# BigClown_Sensor_adapter_v0_2.net
KiCad netlist of a schematic drawn in EAGLE
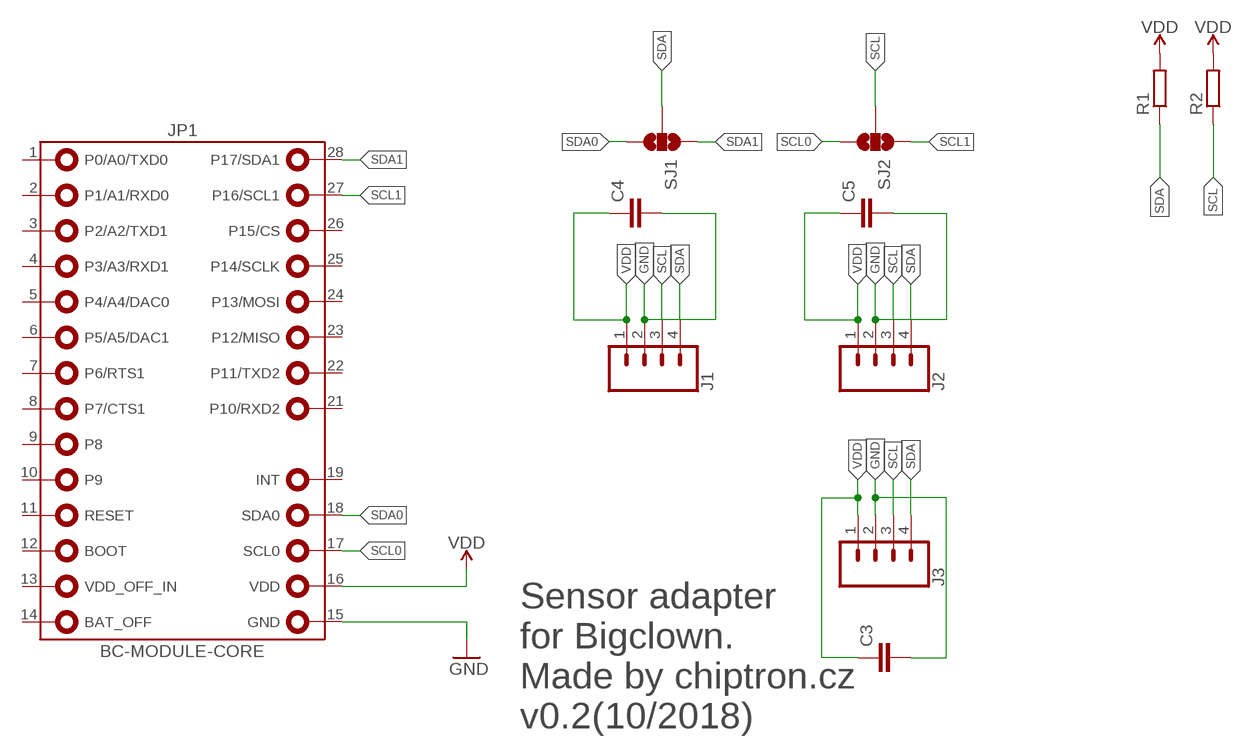
[diagram p0: schematic, sheet 1]

(export (version "E")
  (design (tool "Eeschema 10.0.6"))
  (components
    (comp (ref "C3")
      (value "C-EUC0805")
      (footprint "eagle-import:C0805")
      (libsource (lib "eagle-import") (part "C-EUC0805"))
    )
    (comp (ref "C4")
      (value "C-EUC0805")
      (footprint "eagle-import:C0805")
      (libsource (lib "eagle-import") (part "C-EUC0805"))
    )
    (comp (ref "C5")
      (value "C-EUC0805")
      (footprint "eagle-import:C0805")
      (libsource (lib "eagle-import") (part "C-EUC0805"))
    )
    (comp (ref "J1")
      (value "CONN_04LONGPADS")
      (footprint "eagle-import:1X04_LONGPADS")
      (libsource (lib "eagle-import") (part "CONN_04LONGPADS"))
    )
    (comp (ref "J2")
      (value "CONN_04LONGPADS")
      (footprint "eagle-import:1X04_LONGPADS")
      (libsource (lib "eagle-import") (part "CONN_04LONGPADS"))
    )
    (comp (ref "J3")
      (value "CONN_04LONGPADS")
      (footprint "eagle-import:1X04_LONGPADS")
      (libsource (lib "eagle-import") (part "CONN_04LONGPADS"))
    )
    (comp (ref "JP1")
      (value "BC-MODULE-CORE")
      (footprint "eagle-import:BC-MODULE-CORE")
      (libsource (lib "eagle-import") (part "BC-MODULE-CORE"))
    )
    (comp (ref "R1")
      (value "R-EU_M0805")
      (footprint "eagle-import:M0805")
      (libsource (lib "eagle-import") (part "R-EU_M0805"))
    )
    (comp (ref "R2")
      (value "R-EU_M0805")
      (footprint "eagle-import:M0805")
      (libsource (lib "eagle-import") (part "R-EU_M0805"))
    )
    (comp (ref "SJ1")
      (value "SOLDERJUMPER_2WAYS")
      (footprint "eagle-import:SJ_3")
      (libsource (lib "eagle-import") (part "SOLDERJUMPER_2WAYS"))
    )
    (comp (ref "SJ2")
      (value "SOLDERJUMPER_2WAYS")
      (footprint "eagle-import:SJ_3")
      (libsource (lib "eagle-import") (part "SOLDERJUMPER_2WAYS"))
    )
  )
  (nets
    (net (code "1") (name "GND") (class "Default")
      (node (ref "C3") (pin "2") (pinfunction "2_2") (pintype "passive"))
      (node (ref "C4") (pin "2") (pinfunction "2_2") (pintype "passive"))
      (node (ref "C5") (pin "2") (pinfunction "2_2") (pintype "passive"))
      (node (ref "J1") (pin "2") (pinfunction "2_2") (pintype "passive"))
      (node (ref "J2") (pin "2") (pinfunction "2_2") (pintype "passive"))
      (node (ref "J3") (pin "2") (pinfunction "2_2") (pintype "passive"))
      (node (ref "JP1") (pin "15") (pinfunction "GND_15") (pintype "passive"))
    )
    (net (code "2") (name "SCL") (class "Default")
      (node (ref "J1") (pin "3") (pinfunction "3_3") (pintype "passive"))
      (node (ref "J2") (pin "3") (pinfunction "3_3") (pintype "passive"))
      (node (ref "J3") (pin "3") (pinfunction "3_3") (pintype "passive"))
      (node (ref "R2") (pin "1") (pinfunction "1_1") (pintype "passive"))
      (node (ref "SJ2") (pin "2") (pinfunction "2_2") (pintype "passive"))
    )
    (net (code "3") (name "SCL0") (class "Default")
      (node (ref "JP1") (pin "17") (pinfunction "SCL0_17") (pintype "passive"))
      (node (ref "SJ2") (pin "3") (pinfunction "3_3") (pintype "passive"))
    )
    (net (code "4") (name "SCL1") (class "Default")
      (node (ref "JP1") (pin "27") (pinfunction "P16/SCL1_27") (pintype "passive"))
      (node (ref "SJ2") (pin "1") (pinfunction "1_1") (pintype "passive"))
    )
    (net (code "5") (name "SDA") (class "Default")
      (node (ref "J1") (pin "4") (pinfunction "4_4") (pintype "passive"))
      (node (ref "J2") (pin "4") (pinfunction "4_4") (pintype "passive"))
      (node (ref "J3") (pin "4") (pinfunction "4_4") (pintype "passive"))
      (node (ref "R1") (pin "1") (pinfunction "1_1") (pintype "passive"))
      (node (ref "SJ1") (pin "2") (pinfunction "2_2") (pintype "passive"))
    )
    (net (code "6") (name "SDA0") (class "Default")
      (node (ref "JP1") (pin "18") (pinfunction "SDA0_18") (pintype "passive"))
      (node (ref "SJ1") (pin "3") (pinfunction "3_3") (pintype "passive"))
    )
    (net (code "7") (name "SDA1") (class "Default")
      (node (ref "JP1") (pin "28") (pinfunction "P17/SDA1_28") (pintype "passive"))
      (node (ref "SJ1") (pin "1") (pinfunction "1_1") (pintype "passive"))
    )
    (net (code "8") (name "VDD") (class "Default")
      (node (ref "C3") (pin "1") (pinfunction "1_1") (pintype "passive"))
      (node (ref "C4") (pin "1") (pinfunction "1_1") (pintype "passive"))
      (node (ref "C5") (pin "1") (pinfunction "1_1") (pintype "passive"))
      (node (ref "J1") (pin "1") (pinfunction "1_1") (pintype "passive"))
      (node (ref "J2") (pin "1") (pinfunction "1_1") (pintype "passive"))
      (node (ref "J3") (pin "1") (pinfunction "1_1") (pintype "passive"))
      (node (ref "JP1") (pin "16") (pinfunction "VDD_16") (pintype "passive"))
      (node (ref "R1") (pin "2") (pinfunction "2_2") (pintype "passive"))
      (node (ref "R2") (pin "2") (pinfunction "2_2") (pintype "passive"))
    )
    (net (code "9") (name "unconnected-(JP1-BAT_OFF-Pad14)") (class "Default")
      (node (ref "JP1") (pin "14") (pinfunction "BAT_OFF_14") (pintype "passive"))
    )
    (net (code "10") (name "unconnected-(JP1-BOOT-Pad12)") (class "Default")
      (node (ref "JP1") (pin "12") (pinfunction "BOOT_12") (pintype "passive"))
    )
    (net (code "11") (name "unconnected-(JP1-INT-Pad19)") (class "Default")
      (node (ref "JP1") (pin "19") (pinfunction "INT_19") (pintype "passive"))
    )
    (net (code "12") (name "unconnected-(JP1-P0{slash}A0{slash}TXD0-Pad1)") (class "Default")
      (node (ref "JP1") (pin "1") (pinfunction "P0/A0/TXD0_1") (pintype "passive"))
    )
    (net (code "13") (name "unconnected-(JP1-P1{slash}A1{slash}RXD0-Pad2)") (class "Default")
      (node (ref "JP1") (pin "2") (pinfunction "P1/A1/RXD0_2") (pintype "passive"))
    )
    (net (code "14") (name "unconnected-(JP1-P2{slash}A2{slash}TXD1-Pad3)") (class "Default")
      (node (ref "JP1") (pin "3") (pinfunction "P2/A2/TXD1_3") (pintype "passive"))
    )
    (net (code "15") (name "unconnected-(JP1-P3{slash}A3{slash}RXD1-Pad4)") (class "Default")
      (node (ref "JP1") (pin "4") (pinfunction "P3/A3/RXD1_4") (pintype "passive"))
    )
    (net (code "16") (name "unconnected-(JP1-P4{slash}A4{slash}DAC0-Pad5)") (class "Default")
      (node (ref "JP1") (pin "5") (pinfunction "P4/A4/DAC0_5") (pintype "passive"))
    )
    (net (code "17") (name "unconnected-(JP1-P5{slash}A5{slash}DAC1-Pad6)") (class "Default")
      (node (ref "JP1") (pin "6") (pinfunction "P5/A5/DAC1_6") (pintype "passive"))
    )
    (net (code "18") (name "unconnected-(JP1-P6{slash}RTS1-Pad7)") (class "Default")
      (node (ref "JP1") (pin "7") (pinfunction "P6/RTS1_7") (pintype "passive"))
    )
    (net (code "19") (name "unconnected-(JP1-P7{slash}CTS1-Pad8)") (class "Default")
      (node (ref "JP1") (pin "8") (pinfunction "P7/CTS1_8") (pintype "passive"))
    )
    (net (code "20") (name "unconnected-(JP1-P8-Pad9)") (class "Default")
      (node (ref "JP1") (pin "9") (pinfunction "P8_9") (pintype "passive"))
    )
    (net (code "21") (name "unconnected-(JP1-P9-Pad10)") (class "Default")
      (node (ref "JP1") (pin "10") (pinfunction "P9_10") (pintype "passive"))
    )
    (net (code "22") (name "unconnected-(JP1-P10{slash}RXD2-Pad21)") (class "Default")
      (node (ref "JP1") (pin "21") (pinfunction "P10/RXD2_21") (pintype "passive"))
    )
    (net (code "23") (name "unconnected-(JP1-P11{slash}TXD2-Pad22)") (class "Default")
      (node (ref "JP1") (pin "22") (pinfunction "P11/TXD2_22") (pintype "passive"))
    )
    (net (code "24") (name "unconnected-(JP1-P12{slash}MISO-Pad23)") (class "Default")
      (node (ref "JP1") (pin "23") (pinfunction "P12/MISO_23") (pintype "passive"))
    )
    (net (code "25") (name "unconnected-(JP1-P13{slash}MOSI-Pad24)") (class "Default")
      (node (ref "JP1") (pin "24") (pinfunction "P13/MOSI_24") (pintype "passive"))
    )
    (net (code "26") (name "unconnected-(JP1-P14{slash}SCLK-Pad25)") (class "Default")
      (node (ref "JP1") (pin "25") (pinfunction "P14/SCLK_25") (pintype "passive"))
    )
    (net (code "27") (name "unconnected-(JP1-P15{slash}CS-Pad26)") (class "Default")
      (node (ref "JP1") (pin "26") (pinfunction "P15/CS_26") (pintype "passive"))
    )
    (net (code "28") (name "unconnected-(JP1-RESET-Pad11)") (class "Default")
      (node (ref "JP1") (pin "11") (pinfunction "RESET_11") (pintype "passive"))
    )
    (net (code "29") (name "unconnected-(JP1-VDD_OFF_IN-Pad13)") (class "Default")
      (node (ref "JP1") (pin "13") (pinfunction "VDD_OFF_IN_13") (pintype "passive"))
    )
  )
)
